# PicoHAL_-_w5500.net
KiCad netlist of a schematic drawn in Altium Designer
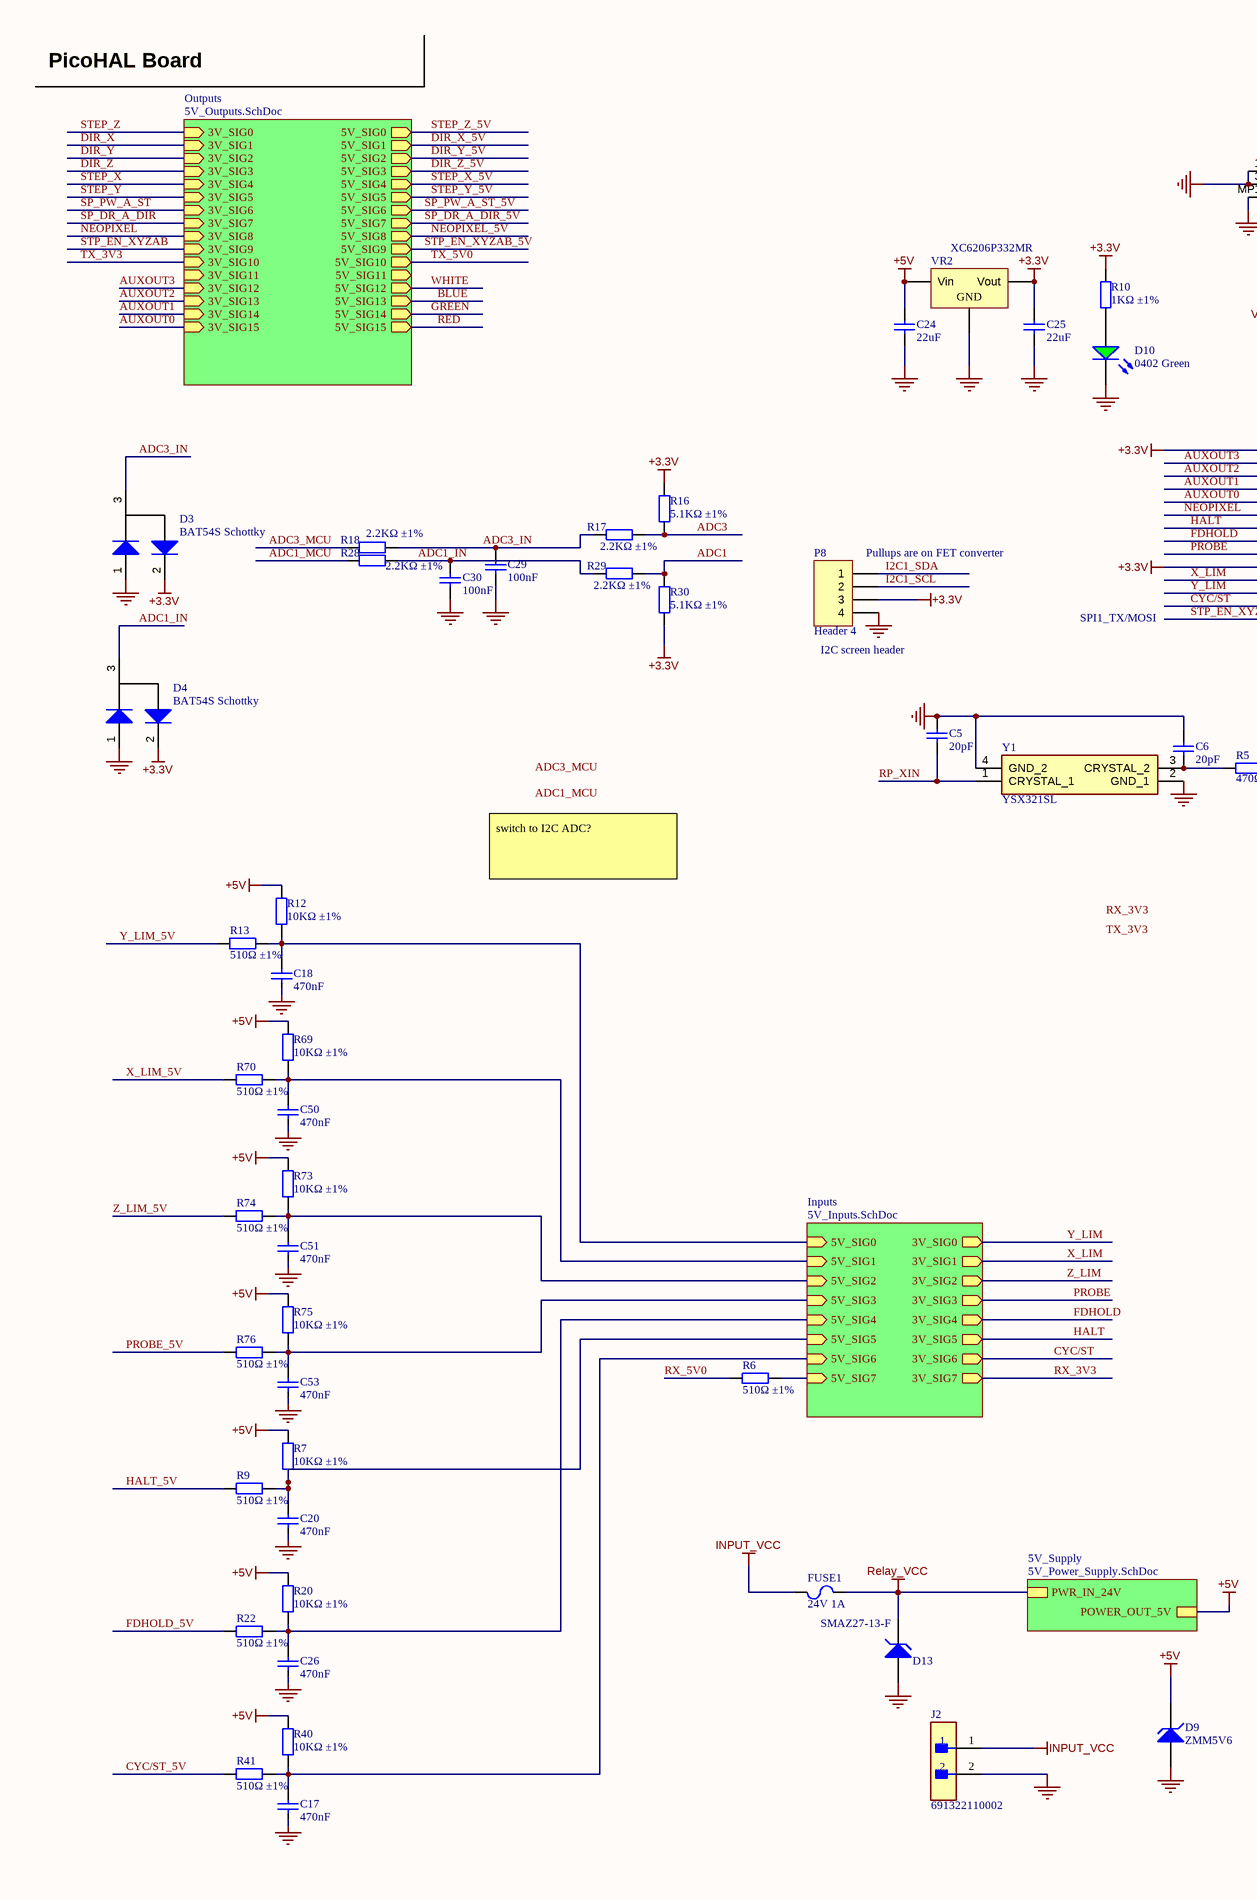
[diagram p0: PicoHAL - w5500.SchDoc, left]
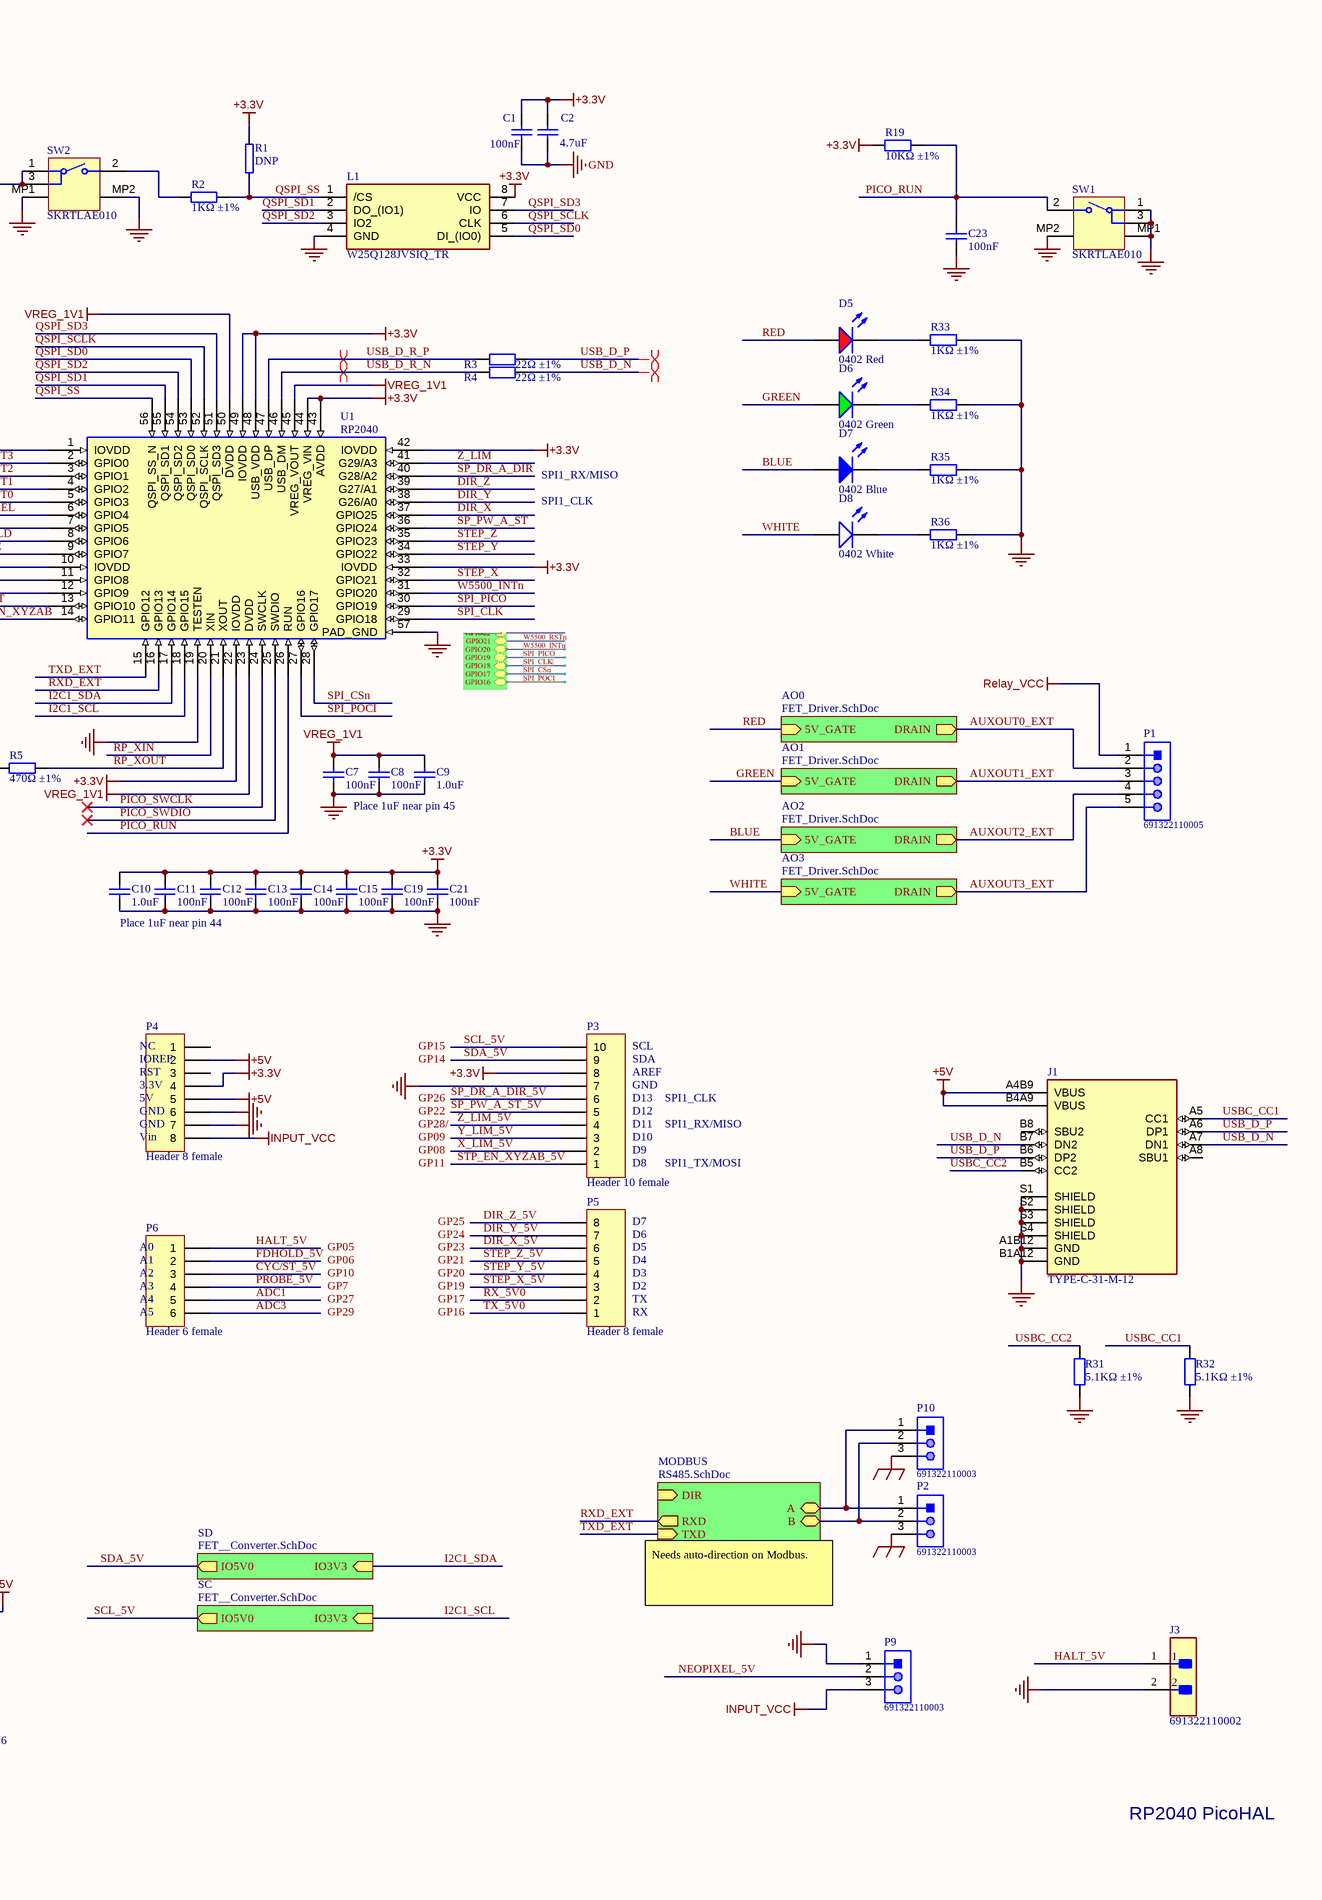
[diagram p1: PicoHAL - w5500.SchDoc, right]

(export (version "E")
  (design (tool "Eeschema 10.0.6"))
  (components
    (comp (ref "C1")
      (value "100nF")
      (footprint "0402_C")
      (description "Chip capacitors")
      (fields
        (field (name "MANUFACTURER") "Samsung Electro-Mechanics")
        (field (name "PARTNUMBER") "CL05B104KO5NNNC")
      )
      (libsource (lib "Cap") (part "0402 100nF (104) 10% 16V"))
    )
    (comp (ref "C2")
      (value "4.7uF")
      (footprint "0402_C")
      (description "Chip capacitor")
      (fields
        (field (name "MANUFACTURER") "Samsung Electro-Mechanics")
        (field (name "PARTNUMBER") "CL05A475MP5NRNC")
      )
      (libsource (lib "Cap") (part "0402 4.7uF (475) 20% 10V"))
    )
    (comp (ref "C5")
      (value "20pF")
      (footprint "0402_C")
      (description "Chip capacitors")
      (fields
        (field (name "MANUFACTURER") "Guangdong Fenghua Advanced Tech")
        (field (name "PARTNUMBER") "0402CG200J500NT")
      )
      (libsource (lib "Cap") (part "0402 20pF (200) 5% 50V"))
    )
    (comp (ref "C6")
      (value "20pF")
      (footprint "0402_C")
      (description "Chip capacitors")
      (fields
        (field (name "MANUFACTURER") "Guangdong Fenghua Advanced Tech")
        (field (name "PARTNUMBER") "0402CG200J500NT")
      )
      (libsource (lib "Cap") (part "0402 20pF (200) 5% 50V"))
    )
    (comp (ref "C7")
      (value "100nF")
      (footprint "0402_C")
      (description "Chip capacitors")
      (fields
        (field (name "MANUFACTURER") "Samsung Electro-Mechanics")
        (field (name "PARTNUMBER") "CL05B104KO5NNNC")
      )
      (libsource (lib "Cap") (part "0402 100nF (104) 10% 16V"))
    )
    (comp (ref "C8")
      (value "100nF")
      (footprint "0402_C")
      (description "Chip capacitors")
      (fields
        (field (name "MANUFACTURER") "Samsung Electro-Mechanics")
        (field (name "PARTNUMBER") "CL05B104KO5NNNC")
      )
      (libsource (lib "Cap") (part "0402 100nF (104) 10% 16V"))
    )
    (comp (ref "C9")
      (value "1.0uF")
      (footprint "0402_C")
      (description "Chip capacitor")
      (fields
        (field (name "MANUFACTURER") "Samsung Electro-Mechanics")
        (field (name "PARTNUMBER") "CL05A105KA5NQNC")
      )
      (libsource (lib "Cap") (part "0402 1.0uF (105) 10% 25V"))
    )
    (comp (ref "C10")
      (value "1.0uF")
      (footprint "0402_C")
      (description "Chip capacitor")
      (fields
        (field (name "MANUFACTURER") "Samsung Electro-Mechanics")
        (field (name "PARTNUMBER") "CL05A105KA5NQNC")
      )
      (libsource (lib "Cap") (part "0402 1.0uF (105) 10% 25V"))
    )
    (comp (ref "C11")
      (value "100nF")
      (footprint "0402_C")
      (description "Chip capacitors")
      (fields
        (field (name "MANUFACTURER") "Samsung Electro-Mechanics")
        (field (name "PARTNUMBER") "CL05B104KO5NNNC")
      )
      (libsource (lib "Cap") (part "0402 100nF (104) 10% 16V"))
    )
    (comp (ref "C12")
      (value "100nF")
      (footprint "0402_C")
      (description "Chip capacitors")
      (fields
        (field (name "MANUFACTURER") "Samsung Electro-Mechanics")
        (field (name "PARTNUMBER") "CL05B104KO5NNNC")
      )
      (libsource (lib "Cap") (part "0402 100nF (104) 10% 16V"))
    )
    (comp (ref "C13")
      (value "100nF")
      (footprint "0402_C")
      (description "Chip capacitors")
      (fields
        (field (name "MANUFACTURER") "Samsung Electro-Mechanics")
        (field (name "PARTNUMBER") "CL05B104KO5NNNC")
      )
      (libsource (lib "Cap") (part "0402 100nF (104) 10% 16V"))
    )
    (comp (ref "C14")
      (value "100nF")
      (footprint "0402_C")
      (description "Chip capacitors")
      (fields
        (field (name "MANUFACTURER") "Samsung Electro-Mechanics")
        (field (name "PARTNUMBER") "CL05B104KO5NNNC")
      )
      (libsource (lib "Cap") (part "0402 100nF (104) 10% 16V"))
    )
    (comp (ref "C15")
      (value "100nF")
      (footprint "0402_C")
      (description "Chip capacitors")
      (fields
        (field (name "MANUFACTURER") "Samsung Electro-Mechanics")
        (field (name "PARTNUMBER") "CL05B104KO5NNNC")
      )
      (libsource (lib "Cap") (part "0402 100nF (104) 10% 16V"))
    )
    (comp (ref "C17")
      (value "470nF")
      (footprint "0402_C")
      (description "Chip capacitors")
      (fields
        (field (name "MANUFACTURER") "Samsung Electro-Mechanics")
        (field (name "PARTNUMBER") "CL05A474KP5NNNC")
      )
      (libsource (lib "Cap") (part "0402 470nF (474) 10% 10V"))
    )
    (comp (ref "C18")
      (value "470nF")
      (footprint "0402_C")
      (description "Chip capacitors")
      (fields
        (field (name "MANUFACTURER") "Samsung Electro-Mechanics")
        (field (name "PARTNUMBER") "CL05A474KP5NNNC")
      )
      (libsource (lib "Cap") (part "0402 470nF (474) 10% 10V"))
    )
    (comp (ref "C19")
      (value "100nF")
      (footprint "0402_C")
      (description "Chip capacitors")
      (fields
        (field (name "MANUFACTURER") "Samsung Electro-Mechanics")
        (field (name "PARTNUMBER") "CL05B104KO5NNNC")
      )
      (libsource (lib "Cap") (part "0402 100nF (104) 10% 16V"))
    )
    (comp (ref "C20")
      (value "470nF")
      (footprint "0402_C")
      (description "Chip capacitors")
      (fields
        (field (name "MANUFACTURER") "Samsung Electro-Mechanics")
        (field (name "PARTNUMBER") "CL05A474KP5NNNC")
      )
      (libsource (lib "Cap") (part "0402 470nF (474) 10% 10V"))
    )
    (comp (ref "C21")
      (value "100nF")
      (footprint "0402_C")
      (description "Chip capacitors")
      (fields
        (field (name "MANUFACTURER") "Samsung Electro-Mechanics")
        (field (name "PARTNUMBER") "CL05B104KO5NNNC")
      )
      (libsource (lib "Cap") (part "0402 100nF (104) 10% 16V"))
    )
    (comp (ref "C23")
      (value "100nF")
      (footprint "0402_C")
      (description "Chip capacitors")
      (fields
        (field (name "MANUFACTURER") "Samsung Electro-Mechanics")
        (field (name "PARTNUMBER") "CL05B104KO5NNNC")
      )
      (libsource (lib "Cap") (part "0402 100nF (104) 10% 16V"))
    )
    (comp (ref "C24")
      (value "22uF")
      (footprint "0805_C")
      (description "Chip capacitors")
      (fields
        (field (name "MANUFACTURER") "Samsung Electro-Mechanics")
        (field (name "PARTNUMBER") "CL21A226MAQNNNE")
      )
      (libsource (lib "Cap") (part "0805 22uF (226) 20% 25V"))
    )
    (comp (ref "C25")
      (value "22uF")
      (footprint "0805_C")
      (description "Chip capacitors")
      (fields
        (field (name "MANUFACTURER") "Samsung Electro-Mechanics")
        (field (name "PARTNUMBER") "CL21A226MAQNNNE")
      )
      (libsource (lib "Cap") (part "0805 22uF (226) 20% 25V"))
    )
    (comp (ref "C26")
      (value "470nF")
      (footprint "0402_C")
      (description "Chip capacitors")
      (fields
        (field (name "MANUFACTURER") "Samsung Electro-Mechanics")
        (field (name "PARTNUMBER") "CL05A474KP5NNNC")
      )
      (libsource (lib "Cap") (part "0402 470nF (474) 10% 10V"))
    )
    (comp (ref "C29")
      (value "100nF")
      (footprint "0402_C")
      (description "Chip capacitors")
      (fields
        (field (name "MANUFACTURER") "Samsung Electro-Mechanics")
        (field (name "PARTNUMBER") "CL05B104KO5NNNC")
      )
      (libsource (lib "Cap") (part "0402 100nF (104) 10% 16V"))
    )
    (comp (ref "C30")
      (value "100nF")
      (footprint "0402_C")
      (description "Chip capacitors")
      (fields
        (field (name "MANUFACTURER") "Samsung Electro-Mechanics")
        (field (name "PARTNUMBER") "CL05B104KO5NNNC")
      )
      (libsource (lib "Cap") (part "0402 100nF (104) 10% 16V"))
    )
    (comp (ref "C50")
      (value "470nF")
      (footprint "0402_C")
      (description "Chip capacitors")
      (fields
        (field (name "MANUFACTURER") "Samsung Electro-Mechanics")
        (field (name "PARTNUMBER") "CL05A474KP5NNNC")
      )
      (libsource (lib "Cap") (part "0402 470nF (474) 10% 10V"))
    )
    (comp (ref "C51")
      (value "470nF")
      (footprint "0402_C")
      (description "Chip capacitors")
      (fields
        (field (name "MANUFACTURER") "Samsung Electro-Mechanics")
        (field (name "PARTNUMBER") "CL05A474KP5NNNC")
      )
      (libsource (lib "Cap") (part "0402 470nF (474) 10% 10V"))
    )
    (comp (ref "C53")
      (value "470nF")
      (footprint "0402_C")
      (description "Chip capacitors")
      (fields
        (field (name "MANUFACTURER") "Samsung Electro-Mechanics")
        (field (name "PARTNUMBER") "CL05A474KP5NNNC")
      )
      (libsource (lib "Cap") (part "0402 470nF (474) 10% 10V"))
    )
    (comp (ref "D3")
      (value "BAT54S Schottky")
      (footprint "SOT-23(SOT-23-3)")
      (description "30V Dual 200mA 800mV@100mA SOT-23 Schottky Barrier Diodes (SBD) ROHS")
      (libsource (lib "Diode") (part "SOT-23 BAT54S"))
    )
    (comp (ref "D4")
      (value "BAT54S Schottky")
      (footprint "SOT-23(SOT-23-3)")
      (description "30V Dual 200mA 800mV@100mA SOT-23 Schottky Barrier Diodes (SBD) ROHS")
      (libsource (lib "Diode") (part "SOT-23 BAT54S"))
    )
    (comp (ref "D5")
      (value "0402 Red")
      (footprint "LED 0402_1005 RED")
      (description "LED")
      (libsource (lib "LED") (part "0402 LED Red"))
    )
    (comp (ref "D6")
      (value "0402 Green")
      (footprint "LED 0402_1005 RED")
      (description "LED")
      (libsource (lib "LED") (part "0402 LED Green"))
    )
    (comp (ref "D7")
      (value "0402 Blue")
      (footprint "LED 0402_1005 RED")
      (description "LED")
      (libsource (lib "LED") (part "0402 LED Blue"))
    )
    (comp (ref "D8")
      (value "0402 White")
      (footprint "LED 0402_1005 RED")
      (description "LED")
      (libsource (lib "LED") (part "0402 LED White"))
    )
    (comp (ref "D9")
      (value "ZMM5V6")
      (footprint "LL-34")
      (description "500mW - 0.1uA @ 1V 5.6V LL-34 Zener Diodes ROHS")
      (libsource (lib "Zener") (part "LL-34 ZMM5V6"))
    )
    (comp (ref "D10")
      (value "0402 Green")
      (footprint "LED 0402_1005 RED")
      (description "LED")
      (libsource (lib "LED") (part "0402 LED Green"))
    )
    (comp (ref "D13")
      (value "SMAZ27-13-F")
      (footprint "DIOM5226X240N")
      (description "27V ±5% 1W 500nA @ 20.5V SMA(DO-214AC) Zener Diodes RoHS")
      (libsource (lib "PrintNC_GRBLHAL_Breakout") (part "BZT52C27"))
    )
    (comp (ref "FUSE1")
      (value "24V 1A")
      (footprint "1206_C")
      (description "24V 1A 0.1s 1206 PTC Resettable Fuses RoHS")
      (fields
        (field (name "MANUFACTURER") "Jinrui Electronic Materials Co.")
        (field (name "PARTNUMBER") "JK-nSMD050-24")
      )
      (libsource (lib "PrintNC_GRBLHAL_Breakout") (part "JK-nSMD050-24"))
    )
    (comp (ref "J1")
      (value "TYPE-C-31-M-12")
      (footprint "HRO_TYPE-C-31-M-12")
      (description "USB Connectors 24 Receptacle 1 8.94*7.3mm RoHS")
      (fields (field (name "MF") "HRO Electronics Co., Ltd."))
      (libsource (lib "Universal_CNC_Breakout") (part "TYPE-C-31-M-12"))
    )
    (comp (ref "J2")
      (value "691322110002")
      (footprint "FP-691322110002-MFG")
      (description "TERM BLOCK HDR 2POS 90DEG 3.5MM")
      (fields (field (name "VOLTAGE") "300V"))
      (libsource (lib "Altium Content Vault") (part "3bc925449376181038e59eaffc5286c"))
    )
    (comp (ref "J3")
      (value "691322110002")
      (footprint "FP-691322110002-MFG")
      (description "TERM BLOCK HDR 2POS 90DEG 3.5MM")
      (fields (field (name "VOLTAGE") "300V"))
      (libsource (lib "") (part "3bc925449376181038e59eaffc5286c_1"))
    )
    (comp (ref "L1")
      (value "W25Q128JVSIQ_TR")
      (footprint "SamacSys:SOIC127P780X195-8N")
      (description "Inductor")
      (fields
        (field (name "MANUFACTURER_PART_NUMBER") "W25Q128JVSIQ TR")
        (field (name "MOUSER PART NUMBER") "454-W25Q128JVSIQTR")
      )
      (libsource (lib "*") (part "W25Q128JVSIQ_TR"))
    )
    (comp (ref "P1")
      (value "691322110005")
      (footprint "691322110005")
      (description "Serie 3221 - 3.50mm Horizontal PCB Header WR-TBL, 5 pin")
      (fields (field (name "MANUFACTURER") "Wurth Elektronik") (field (name "PUBLISHER") "WurthElektronik"))
      (libsource (lib "Altium Content Vault") (part "WE-CN-1P-M-R5"))
    )
    (comp (ref "P2")
      (value "691322110003")
      (footprint "691322110003")
      (description "Serie 3221 - 3.50mm Horizontal PCB Header WR-TBL, 3 pin")
      (fields (field (name "MANUFACTURER") "Wurth Elektronik") (field (name "PUBLISHER") "WurthElektronik"))
      (libsource (lib "Altium Content Vault") (part "WE-CN-1P-M-R3"))
    )
    (comp (ref "P3")
      (value "Header 10 female")
      (footprint "HDR1X10")
      (description "Header, 10-Pin")
      (fields (field (name "PUBLISHER") "Altium Limited"))
      (libsource (lib "Miscellaneous Connectors") (part "Header 10"))
    )
    (comp (ref "P4")
      (value "Header 8 female")
      (footprint "HDR1X8")
      (description "Header, 8-Pin")
      (fields (field (name "PUBLISHER") "Altium Limited"))
      (libsource (lib "") (part "Header 8_1"))
    )
    (comp (ref "P5")
      (value "Header 8 female")
      (footprint "HDR1X8")
      (description "Header, 8-Pin")
      (fields (field (name "PUBLISHER") "Altium Limited"))
      (libsource (lib "Miscellaneous Connectors") (part "Header 8"))
    )
    (comp (ref "P6")
      (value "Header 6 female")
      (footprint "HDR1X6")
      (description "Header, 6-Pin")
      (fields (field (name "PUBLISHER") "Altium Limited"))
      (libsource (lib "Miscellaneous Connectors") (part "Header 6"))
    )
    (comp (ref "P8")
      (value "Header 4")
      (footprint "HDR1X4")
      (description "Header, 4-Pin F")
      (fields (field (name "PUBLISHER") "Altium Limited"))
      (libsource (lib "PrintNC_GRBLHAL_Breakout") (part "Header 4"))
    )
    (comp (ref "P9")
      (value "691322110003")
      (footprint "691322110003")
      (description "Serie 3221 - 3.50mm Horizontal PCB Header WR-TBL, 3 pin")
      (fields (field (name "MANUFACTURER") "Wurth Elektronik") (field (name "PUBLISHER") "WurthElektronik"))
      (libsource (lib "Altium Content Vault") (part "WE-CN-1P-M-R3"))
    )
    (comp (ref "P10")
      (value "691322110003")
      (footprint "691322110003")
      (description "Serie 3221 - 3.50mm Horizontal PCB Header WR-TBL, 3 pin")
      (fields (field (name "MANUFACTURER") "Wurth Elektronik") (field (name "PUBLISHER") "WurthElektronik"))
      (libsource (lib "Altium Content Vault") (part "WE-CN-1P-M-R3"))
    )
    (comp (ref "R1")
      (value "DNP")
      (footprint "0402")
      (description "Resistor, ±5%, 0.05W")
      (fields (field (name "PART NUMBER") "R0201-0R") (field (name "PUBLISHER") "Nordic Semiconductor"))
      (libsource (lib "Passives") (part "RES"))
    )
    (comp (ref "R2")
      (value "1KΩ ±1%")
      (footprint "0402_R")
      (description "Chip resistor")
      (fields (field (name "MANUFACTURER") "Uniroyal Elec") (field (name "PARTNUMBER") "0402WGF1001TCE"))
      (libsource (lib "RES") (part "0402 1K (1001) 1%"))
    )
    (comp (ref "R3")
      (value "22Ω ±1%")
      (footprint "0402_R")
      (description "Chip resistor")
      (fields (field (name "MANUFACTURER") "Uniroyal Elec") (field (name "PARTNUMBER") "0402WGF220JTCE"))
      (libsource (lib "RES") (part "0402 22R (22R0) 1%"))
    )
    (comp (ref "R4")
      (value "22Ω ±1%")
      (footprint "0402_R")
      (description "Chip resistor")
      (fields (field (name "MANUFACTURER") "Uniroyal Elec") (field (name "PARTNUMBER") "0402WGF220JTCE"))
      (libsource (lib "RES") (part "0402 22R (22R0) 1%"))
    )
    (comp (ref "R5")
      (value "470Ω ±1%")
      (footprint "0402_R")
      (description "Chip resistor")
      (fields (field (name "MANUFACTURER") "Uniroyal Elec") (field (name "PARTNUMBER") "0402WGF4700TCE"))
      (libsource (lib "RES") (part "0402 470R (4700) 1%"))
    )
    (comp (ref "R6")
      (value "510Ω ±1%")
      (footprint "0402_R")
      (description "Chip resistor")
      (fields (field (name "MANUFACTURER") "Uniroyal Elec") (field (name "PARTNUMBER") "0402WGF5100TCE"))
      (libsource (lib "RES") (part "0402 510R (5100) 1%"))
    )
    (comp (ref "R7")
      (value "10KΩ ±1%")
      (footprint "0402_R")
      (description "Chip resistor")
      (fields (field (name "MANUFACTURER") "Uniroyal Elec") (field (name "PARTNUMBER") "0402WGF1002TCE"))
      (libsource (lib "RES") (part "0402 10K (1002) 1%"))
    )
    (comp (ref "R9")
      (value "510Ω ±1%")
      (footprint "0402_R")
      (description "Chip resistor")
      (fields (field (name "MANUFACTURER") "Uniroyal Elec") (field (name "PARTNUMBER") "0402WGF5100TCE"))
      (libsource (lib "RES") (part "0402 510R (5100) 1%"))
    )
    (comp (ref "R10")
      (value "1KΩ ±1%")
      (footprint "0402_R")
      (description "Chip resistor")
      (fields (field (name "MANUFACTURER") "Uniroyal Elec") (field (name "PARTNUMBER") "0402WGF1001TCE"))
      (libsource (lib "") (part "0402 1K (1001) 1%_1"))
    )
    (comp (ref "R12")
      (value "10KΩ ±1%")
      (footprint "0402_R")
      (description "Chip resistor")
      (fields (field (name "MANUFACTURER") "Uniroyal Elec") (field (name "PARTNUMBER") "0402WGF1002TCE"))
      (libsource (lib "RES") (part "0402 10K (1002) 1%"))
    )
    (comp (ref "R13")
      (value "510Ω ±1%")
      (footprint "0402_R")
      (description "Chip resistor")
      (fields (field (name "MANUFACTURER") "Uniroyal Elec") (field (name "PARTNUMBER") "0402WGF5100TCE"))
      (libsource (lib "RES") (part "0402 510R (5100) 1%"))
    )
    (comp (ref "R16")
      (value "5.1KΩ ±1%")
      (footprint "0402_R")
      (description "Chip resistor")
      (fields (field (name "MANUFACTURER") "Uniroyal Elec") (field (name "PARTNUMBER") "0402WGF5101TCE"))
      (libsource (lib "RES") (part "0402 5.1K (5101) 1%"))
    )
    (comp (ref "R17")
      (value "2.2KΩ ±1%")
      (footprint "0402_R")
      (description "Chip resistor")
      (fields (field (name "MANUFACTURER") "Uniroyal Elec") (field (name "PARTNUMBER") "0402WGF2201TCE"))
      (libsource (lib "RES") (part "0402 2.2K (2201) 1%"))
    )
    (comp (ref "R18")
      (value "2.2KΩ ±1%")
      (footprint "0402_R")
      (description "Chip resistor")
      (fields (field (name "MANUFACTURER") "Uniroyal Elec") (field (name "PARTNUMBER") "0402WGF2201TCE"))
      (libsource (lib "RES") (part "0402 2.2K (2201) 1%"))
    )
    (comp (ref "R19")
      (value "10KΩ ±1%")
      (footprint "0402_R")
      (description "Chip resistor")
      (fields (field (name "MANUFACTURER") "Uniroyal Elec") (field (name "PARTNUMBER") "0402WGF1002TCE"))
      (libsource (lib "") (part "0402 10K (1002) 1%_1"))
    )
    (comp (ref "R20")
      (value "10KΩ ±1%")
      (footprint "0402_R")
      (description "Chip resistor")
      (fields (field (name "MANUFACTURER") "Uniroyal Elec") (field (name "PARTNUMBER") "0402WGF1002TCE"))
      (libsource (lib "RES") (part "0402 10K (1002) 1%"))
    )
    (comp (ref "R22")
      (value "510Ω ±1%")
      (footprint "0402_R")
      (description "Chip resistor")
      (fields (field (name "MANUFACTURER") "Uniroyal Elec") (field (name "PARTNUMBER") "0402WGF5100TCE"))
      (libsource (lib "RES") (part "0402 510R (5100) 1%"))
    )
    (comp (ref "R28")
      (value "2.2KΩ ±1%")
      (footprint "0402_R")
      (description "Chip resistor")
      (fields (field (name "MANUFACTURER") "Uniroyal Elec") (field (name "PARTNUMBER") "0402WGF2201TCE"))
      (libsource (lib "RES") (part "0402 2.2K (2201) 1%"))
    )
    (comp (ref "R29")
      (value "2.2KΩ ±1%")
      (footprint "0402_R")
      (description "Chip resistor")
      (fields (field (name "MANUFACTURER") "Uniroyal Elec") (field (name "PARTNUMBER") "0402WGF2201TCE"))
      (libsource (lib "RES") (part "0402 2.2K (2201) 1%"))
    )
    (comp (ref "R30")
      (value "5.1KΩ ±1%")
      (footprint "0402_R")
      (description "Chip resistor")
      (fields (field (name "MANUFACTURER") "Uniroyal Elec") (field (name "PARTNUMBER") "0402WGF5101TCE"))
      (libsource (lib "RES") (part "0402 5.1K (5101) 1%"))
    )
    (comp (ref "R31")
      (value "5.1KΩ ±1%")
      (footprint "0402_R")
      (description "Chip resistor")
      (fields (field (name "MANUFACTURER") "Uniroyal Elec") (field (name "PARTNUMBER") "0402WGF5101TCE"))
      (libsource (lib "RES") (part "0402 5.1K (5101) 1%"))
    )
    (comp (ref "R32")
      (value "5.1KΩ ±1%")
      (footprint "0402_R")
      (description "Chip resistor")
      (fields (field (name "MANUFACTURER") "Uniroyal Elec") (field (name "PARTNUMBER") "0402WGF5101TCE"))
      (libsource (lib "RES") (part "0402 5.1K (5101) 1%"))
    )
    (comp (ref "R33")
      (value "1KΩ ±1%")
      (footprint "0402_R")
      (description "Chip resistor")
      (fields (field (name "MANUFACTURER") "Uniroyal Elec") (field (name "PARTNUMBER") "0402WGF1001TCE"))
      (libsource (lib "RES") (part "0402 1K (1001) 1%"))
    )
    (comp (ref "R34")
      (value "1KΩ ±1%")
      (footprint "0402_R")
      (description "Chip resistor")
      (fields (field (name "MANUFACTURER") "Uniroyal Elec") (field (name "PARTNUMBER") "0402WGF1001TCE"))
      (libsource (lib "RES") (part "0402 1K (1001) 1%"))
    )
    (comp (ref "R35")
      (value "1KΩ ±1%")
      (footprint "0402_R")
      (description "Chip resistor")
      (fields (field (name "MANUFACTURER") "Uniroyal Elec") (field (name "PARTNUMBER") "0402WGF1001TCE"))
      (libsource (lib "RES") (part "0402 1K (1001) 1%"))
    )
    (comp (ref "R36")
      (value "1KΩ ±1%")
      (footprint "0402_R")
      (description "Chip resistor")
      (fields (field (name "MANUFACTURER") "Uniroyal Elec") (field (name "PARTNUMBER") "0402WGF1001TCE"))
      (libsource (lib "RES") (part "0402 1K (1001) 1%"))
    )
    (comp (ref "R40")
      (value "10KΩ ±1%")
      (footprint "0402_R")
      (description "Chip resistor")
      (fields (field (name "MANUFACTURER") "Uniroyal Elec") (field (name "PARTNUMBER") "0402WGF1002TCE"))
      (libsource (lib "RES") (part "0402 10K (1002) 1%"))
    )
    (comp (ref "R41")
      (value "510Ω ±1%")
      (footprint "0402_R")
      (description "Chip resistor")
      (fields (field (name "MANUFACTURER") "Uniroyal Elec") (field (name "PARTNUMBER") "0402WGF5100TCE"))
      (libsource (lib "RES") (part "0402 510R (5100) 1%"))
    )
    (comp (ref "R69")
      (value "10KΩ ±1%")
      (footprint "0402_R")
      (description "Chip resistor")
      (fields (field (name "MANUFACTURER") "Uniroyal Elec") (field (name "PARTNUMBER") "0402WGF1002TCE"))
      (libsource (lib "RES") (part "0402 10K (1002) 1%"))
    )
    (comp (ref "R70")
      (value "510Ω ±1%")
      (footprint "0402_R")
      (description "Chip resistor")
      (fields (field (name "MANUFACTURER") "Uniroyal Elec") (field (name "PARTNUMBER") "0402WGF5100TCE"))
      (libsource (lib "RES") (part "0402 510R (5100) 1%"))
    )
    (comp (ref "R73")
      (value "10KΩ ±1%")
      (footprint "0402_R")
      (description "Chip resistor")
      (fields (field (name "MANUFACTURER") "Uniroyal Elec") (field (name "PARTNUMBER") "0402WGF1002TCE"))
      (libsource (lib "RES") (part "0402 10K (1002) 1%"))
    )
    (comp (ref "R74")
      (value "510Ω ±1%")
      (footprint "0402_R")
      (description "Chip resistor")
      (fields (field (name "MANUFACTURER") "Uniroyal Elec") (field (name "PARTNUMBER") "0402WGF5100TCE"))
      (libsource (lib "RES") (part "0402 510R (5100) 1%"))
    )
    (comp (ref "R75")
      (value "10KΩ ±1%")
      (footprint "0402_R")
      (description "Chip resistor")
      (fields (field (name "MANUFACTURER") "Uniroyal Elec") (field (name "PARTNUMBER") "0402WGF1002TCE"))
      (libsource (lib "RES") (part "0402 10K (1002) 1%"))
    )
    (comp (ref "R76")
      (value "510Ω ±1%")
      (footprint "0402_R")
      (description "Chip resistor")
      (fields (field (name "MANUFACTURER") "Uniroyal Elec") (field (name "PARTNUMBER") "0402WGF5100TCE"))
      (libsource (lib "RES") (part "0402 510R (5100) 1%"))
    )
    (comp (ref "SW1")
      (value "SKRTLAE010")
      (footprint "ALPS-SKRTLAE010_V")
      (description "Side Push Type, 250 V, -40 to 90 degC, 3-Pin SMD, RoHS, Tape and Reel")
      (fields (field (name "MANUFACTURER") "ALPS"))
      (libsource (lib "Altium Content Vault") (part "SW_SPST-3_A"))
    )
    (comp (ref "SW2")
      (value "SKRTLAE010")
      (footprint "ALPS-SKRTLAE010_V")
      (description "Side Push Type, 250 V, -40 to 90 degC, 3-Pin SMD, RoHS, Tape and Reel")
      (fields (field (name "MANUFACTURER") "ALPS"))
      (libsource (lib "") (part "SW_SPST-3_A_1"))
    )
    (comp (ref "U1")
      (value "RP2040")
      (footprint "RP2040")
      (description "RP2040 First MCU from RPI")
      (libsource (lib "Universal_CNC_Breakout") (part "RP2040"))
    )
    (comp (ref "VR2")
      (value "XC6206P332MR")
      (footprint "SOT-23-3L")
      (description "200mA 680mV@(100mA) Fixed 3.3V~3.3V Positive 1 6V SOT-23-3L Linear Voltage Regulators (LDO) ROHS")
      (libsource (lib "LDO") (part "SOT-23 XC6206P332MR"))
    )
    (comp (ref "Y1")
      (value "YSX321SL")
      (footprint "SamacSys:YSX321SL")
      (description "Crystal or Oscillator")
      (libsource (lib "*") (part "YSX321SL"))
    )
  )
  (nets
    (net (code "1") (name "+3.3V") (class "Default")
      (node (ref "C1") (pin "2") (pinfunction "2_2") (pintype "passive"))
      (node (ref "C10") (pin "2") (pinfunction "2_2") (pintype "passive"))
      (node (ref "C11") (pin "2") (pinfunction "2_2") (pintype "passive"))
      (node (ref "C12") (pin "2") (pinfunction "2_2") (pintype "passive"))
      (node (ref "C13") (pin "2") (pinfunction "2_2") (pintype "passive"))
      (node (ref "C14") (pin "2") (pinfunction "2_2") (pintype "passive"))
      (node (ref "C15") (pin "2") (pinfunction "2_2") (pintype "passive"))
      (node (ref "C19") (pin "2") (pinfunction "2_2") (pintype "passive"))
      (node (ref "C2") (pin "2") (pinfunction "2_2") (pintype "passive"))
      (node (ref "C21") (pin "2") (pinfunction "2_2") (pintype "passive"))
      (node (ref "C25") (pin "2") (pinfunction "2_2") (pintype "passive"))
      (node (ref "D3") (pin "2") (pinfunction "A_2") (pintype "passive"))
      (node (ref "D4") (pin "2") (pinfunction "A_2") (pintype "passive"))
      (node (ref "L1") (pin "8") (pinfunction "VCC_8") (pintype "passive"))
      (node (ref "P3") (pin "8") (pinfunction "8_8") (pintype "passive"))
      (node (ref "P4") (pin "4") (pinfunction "4_4") (pintype "passive"))
      (node (ref "P8") (pin "3") (pinfunction "3_3") (pintype "passive"))
      (node (ref "R1") (pin "2") (pinfunction "2_2") (pintype "passive"))
      (node (ref "R10") (pin "2") (pinfunction "2_2") (pintype "passive"))
      (node (ref "R16") (pin "1") (pinfunction "1_1") (pintype "passive"))
      (node (ref "R19") (pin "2") (pinfunction "2_2") (pintype "passive"))
      (node (ref "R30") (pin "2") (pinfunction "2_2") (pintype "passive"))
      (node (ref "U1") (pin "1") (pinfunction "IOVDD_1") (pintype "input"))
      (node (ref "U1") (pin "10") (pinfunction "IOVDD_10") (pintype "input"))
      (node (ref "U1") (pin "22") (pinfunction "IOVDD_22") (pintype "input"))
      (node (ref "U1") (pin "33") (pinfunction "IOVDD_33") (pintype "input"))
      (node (ref "U1") (pin "42") (pinfunction "IOVDD_42") (pintype "input"))
      (node (ref "U1") (pin "43") (pinfunction "AVDD_43") (pintype "input"))
      (node (ref "U1") (pin "44") (pinfunction "VREG_VIN_44") (pintype "input"))
      (node (ref "U1") (pin "48") (pinfunction "USB_VDD_48") (pintype "input"))
      (node (ref "U1") (pin "49") (pinfunction "IOVDD_49") (pintype "input"))
      (node (ref "VR2") (pin "2") (pinfunction "Vout_2") (pintype "passive"))
    )
    (net (code "2") (name "+5V") (class "Default")
      (node (ref "C24") (pin "2") (pinfunction "2_2") (pintype "passive"))
      (node (ref "D9") (pin "2") (pinfunction "K_2") (pintype "passive"))
      (node (ref "J1") (pin "A4B9") (pinfunction "VBUS_A4B9") (pintype "power_in"))
      (node (ref "J1") (pin "B4A9") (pinfunction "VBUS_B4A9") (pintype "power_in"))
      (node (ref "P4") (pin "2") (pinfunction "2_2") (pintype "passive"))
      (node (ref "P4") (pin "5") (pinfunction "5_5") (pintype "passive"))
      (node (ref "R12") (pin "2") (pinfunction "2_2") (pintype "passive"))
      (node (ref "R20") (pin "2") (pinfunction "2_2") (pintype "passive"))
      (node (ref "R40") (pin "2") (pinfunction "2_2") (pintype "passive"))
      (node (ref "R69") (pin "2") (pinfunction "2_2") (pintype "passive"))
      (node (ref "R7") (pin "2") (pinfunction "2_2") (pintype "passive"))
      (node (ref "R73") (pin "2") (pinfunction "2_2") (pintype "passive"))
      (node (ref "R75") (pin "2") (pinfunction "2_2") (pintype "passive"))
      (node (ref "VR2") (pin "3") (pinfunction "Vin_3") (pintype "passive"))
    )
    (net (code "4") (name "/5V_SIG0") (class "Default")
      (node (ref "C18") (pin "2") (pinfunction "2_2") (pintype "passive"))
      (node (ref "R12") (pin "1") (pinfunction "1_1") (pintype "passive"))
      (node (ref "R13") (pin "2") (pinfunction "2_2") (pintype "passive"))
    )
    (net (code "5") (name "/5V_SIG1") (class "Default")
      (node (ref "C50") (pin "2") (pinfunction "2_2") (pintype "passive"))
      (node (ref "R69") (pin "1") (pinfunction "1_1") (pintype "passive"))
      (node (ref "R70") (pin "2") (pinfunction "2_2") (pintype "passive"))
    )
    (net (code "6") (name "/5V_SIG2") (class "Default")
      (node (ref "C51") (pin "2") (pinfunction "2_2") (pintype "passive"))
      (node (ref "R73") (pin "1") (pinfunction "1_1") (pintype "passive"))
      (node (ref "R74") (pin "2") (pinfunction "2_2") (pintype "passive"))
    )
    (net (code "7") (name "/5V_SIG3") (class "Default")
      (node (ref "C53") (pin "2") (pinfunction "2_2") (pintype "passive"))
      (node (ref "R75") (pin "1") (pinfunction "1_1") (pintype "passive"))
      (node (ref "R76") (pin "2") (pinfunction "2_2") (pintype "passive"))
    )
    (net (code "8") (name "/5V_SIG4") (class "Default")
      (node (ref "C26") (pin "2") (pinfunction "2_2") (pintype "passive"))
      (node (ref "R20") (pin "1") (pinfunction "1_1") (pintype "passive"))
      (node (ref "R22") (pin "2") (pinfunction "2_2") (pintype "passive"))
    )
    (net (code "9") (name "/5V_SIG5") (class "Default")
      (node (ref "C20") (pin "2") (pinfunction "2_2") (pintype "passive"))
      (node (ref "R7") (pin "1") (pinfunction "1_1") (pintype "passive"))
      (node (ref "R9") (pin "2") (pinfunction "2_2") (pintype "passive"))
    )
    (net (code "10") (name "/5V_SIG6") (class "Default")
      (node (ref "C17") (pin "2") (pinfunction "2_2") (pintype "passive"))
      (node (ref "R40") (pin "1") (pinfunction "1_1") (pintype "passive"))
      (node (ref "R41") (pin "2") (pinfunction "2_2") (pintype "passive"))
    )
    (net (code "11") (name "/5V_SIG7") (class "Default")
      (node (ref "R6") (pin "2") (pinfunction "2_2") (pintype "passive"))
    )
    (net (code "13") (name "/A") (class "Default")
      (node (ref "P10") (pin "1") (pinfunction "1_1") (pintype "passive"))
      (node (ref "P2") (pin "1") (pinfunction "1_1") (pintype "passive"))
    )
    (net (code "14") (name "/ADC1") (class "Default")
      (node (ref "P6") (pin "5") (pinfunction "5_5") (pintype "passive"))
      (node (ref "R29") (pin "2") (pinfunction "2_2") (pintype "passive"))
      (node (ref "R30") (pin "1") (pinfunction "1_1") (pintype "passive"))
    )
    (net (code "15") (name "/ADC1_IN") (class "Default")
      (node (ref "C30") (pin "2") (pinfunction "2_2") (pintype "passive"))
      (node (ref "D4") (pin "3") (pinfunction "K_3") (pintype "passive"))
      (node (ref "R28") (pin "2") (pinfunction "2_2") (pintype "passive"))
      (node (ref "R29") (pin "1") (pinfunction "1_1") (pintype "passive"))
    )
    (net (code "16") (name "/ADC1_MCU") (class "Default")
      (node (ref "R28") (pin "1") (pinfunction "1_1") (pintype "passive"))
    )
    (net (code "17") (name "/ADC3") (class "Default")
      (node (ref "P6") (pin "6") (pinfunction "6_6") (pintype "passive"))
      (node (ref "R16") (pin "2") (pinfunction "2_2") (pintype "passive"))
      (node (ref "R17") (pin "2") (pinfunction "2_2") (pintype "passive"))
    )
    (net (code "18") (name "/ADC3_IN") (class "Default")
      (node (ref "C29") (pin "2") (pinfunction "2_2") (pintype "passive"))
      (node (ref "D3") (pin "3") (pinfunction "K_3") (pintype "passive"))
      (node (ref "R17") (pin "1") (pinfunction "1_1") (pintype "passive"))
      (node (ref "R18") (pin "2") (pinfunction "2_2") (pintype "passive"))
    )
    (net (code "19") (name "/ADC3_MCU") (class "Default")
      (node (ref "R18") (pin "1") (pinfunction "1_1") (pintype "passive"))
    )
    (net (code "20") (name "/AUXOUT0") (class "Default")
      (node (ref "U1") (pin "5") (pinfunction "GPIO3_5") (pintype "bidirectional"))
    )
    (net (code "21") (name "/AUXOUT0_EXT") (class "Default")
      (node (ref "P1") (pin "2") (pinfunction "2_2") (pintype "passive"))
    )
    (net (code "22") (name "/AUXOUT1") (class "Default")
      (node (ref "U1") (pin "4") (pinfunction "GPIO2_4") (pintype "bidirectional"))
    )
    (net (code "23") (name "/AUXOUT1_EXT") (class "Default")
      (node (ref "P1") (pin "3") (pinfunction "3_3") (pintype "passive"))
    )
    (net (code "24") (name "/AUXOUT2") (class "Default")
      (node (ref "U1") (pin "3") (pinfunction "GPIO1_3") (pintype "bidirectional"))
    )
    (net (code "25") (name "/AUXOUT2_EXT") (class "Default")
      (node (ref "P1") (pin "4") (pinfunction "4_4") (pintype "passive"))
    )
    (net (code "26") (name "/AUXOUT3") (class "Default")
      (node (ref "U1") (pin "2") (pinfunction "GPIO0_2") (pintype "bidirectional"))
    )
    (net (code "27") (name "/AUXOUT3_EXT") (class "Default")
      (node (ref "P1") (pin "5") (pinfunction "5_5") (pintype "passive"))
    )
    (net (code "28") (name "/B") (class "Default")
      (node (ref "P10") (pin "2") (pinfunction "2_2") (pintype "passive"))
      (node (ref "P2") (pin "2") (pinfunction "2_2") (pintype "passive"))
    )
    (net (code "29") (name "/BLUE") (class "Default")
      (node (ref "D7") (pin "A") (pinfunction "A_A") (pintype "passive"))
    )
    (net (code "30") (name "/CYC{slash}ST") (class "Default")
      (node (ref "U1") (pin "13") (pinfunction "GPIO10_13") (pintype "bidirectional"))
    )
    (net (code "31") (name "/CYC{slash}ST_5V") (class "Default")
      (node (ref "P6") (pin "3") (pinfunction "3_3") (pintype "passive"))
      (node (ref "R41") (pin "1") (pinfunction "1_1") (pintype "passive"))
    )
    (net (code "33") (name "/DIR_X") (class "Default")
      (node (ref "U1") (pin "37") (pinfunction "GPIO25_37") (pintype "bidirectional"))
    )
    (net (code "34") (name "/DIR_X_5V") (class "Default")
      (node (ref "P5") (pin "6") (pinfunction "6_6") (pintype "passive"))
    )
    (net (code "35") (name "/DIR_Y") (class "Default")
      (node (ref "U1") (pin "38") (pinfunction "G26/A0_38") (pintype "bidirectional"))
    )
    (net (code "36") (name "/DIR_Y_5V") (class "Default")
      (node (ref "P5") (pin "7") (pinfunction "7_7") (pintype "passive"))
    )
    (net (code "37") (name "/DIR_Z") (class "Default")
      (node (ref "U1") (pin "39") (pinfunction "G27/A1_39") (pintype "bidirectional"))
    )
    (net (code "38") (name "/DIR_Z_5V") (class "Default")
      (node (ref "P5") (pin "8") (pinfunction "8_8") (pintype "passive"))
    )
    (net (code "39") (name "/FDHOLD") (class "Default")
      (node (ref "U1") (pin "8") (pinfunction "GPIO6_8") (pintype "bidirectional"))
    )
    (net (code "40") (name "/FDHOLD_5V") (class "Default")
      (node (ref "P6") (pin "2") (pinfunction "2_2") (pintype "passive"))
      (node (ref "R22") (pin "1") (pinfunction "1_1") (pintype "passive"))
    )
    (net (code "41") (name "/GREEN") (class "Default")
      (node (ref "D6") (pin "A") (pinfunction "A_A") (pintype "passive"))
    )
    (net (code "42") (name "/HALT") (class "Default")
      (node (ref "U1") (pin "7") (pinfunction "GPIO5_7") (pintype "bidirectional"))
    )
    (net (code "43") (name "/HALT_5V") (class "Default")
      (node (ref "J3") (pin "1") (pinfunction "1_1") (pintype "passive"))
      (node (ref "P6") (pin "1") (pinfunction "1_1") (pintype "passive"))
      (node (ref "R9") (pin "1") (pinfunction "1_1") (pintype "passive"))
    )
    (net (code "44") (name "/I2C1_SCL") (class "Default")
      (node (ref "P8") (pin "2") (pinfunction "2_2") (pintype "passive"))
      (node (ref "U1") (pin "18") (pinfunction "GPIO15_18") (pintype "input"))
    )
    (net (code "45") (name "/I2C1_SDA") (class "Default")
      (node (ref "P8") (pin "1") (pinfunction "1_1") (pintype "passive"))
      (node (ref "U1") (pin "17") (pinfunction "GPIO14_17") (pintype "input"))
    )
    (net (code "46") (name "/NEOPIXEL") (class "Default")
      (node (ref "U1") (pin "6") (pinfunction "GPIO4_6") (pintype "bidirectional"))
    )
    (net (code "47") (name "/NEOPIXEL_5V") (class "Default")
      (node (ref "P9") (pin "2") (pinfunction "2_2") (pintype "passive"))
    )
    (net (code "48") (name "/PICO_RUN") (class "Default")
      (node (ref "C23") (pin "2") (pinfunction "2_2") (pintype "passive"))
      (node (ref "R19") (pin "1") (pinfunction "1_1") (pintype "passive"))
      (node (ref "SW1") (pin "2") (pinfunction "2_2") (pintype "passive"))
      (node (ref "U1") (pin "26") (pinfunction "RUN_26") (pintype "input"))
    )
    (net (code "49") (name "/PICO_SWCLK") (class "Default")
      (node (ref "U1") (pin "24") (pinfunction "SWCLK_24") (pintype "input+no_connect"))
    )
    (net (code "50") (name "/PICO_SWDIO") (class "Default")
      (node (ref "U1") (pin "25") (pinfunction "SWDIO_25") (pintype "input+no_connect"))
    )
    (net (code "51") (name "/PROBE") (class "Default")
      (node (ref "U1") (pin "9") (pinfunction "GPIO7_9") (pintype "bidirectional"))
    )
    (net (code "52") (name "/PROBE_5V") (class "Default")
      (node (ref "P6") (pin "4") (pinfunction "4_4") (pintype "passive"))
      (node (ref "R76") (pin "1") (pinfunction "1_1") (pintype "passive"))
    )
    (net (code "53") (name "/QSPI_SCLK") (class "Default")
      (node (ref "L1") (pin "6") (pinfunction "CLK_6") (pintype "passive"))
      (node (ref "U1") (pin "52") (pinfunction "QSPI_SCLK_52") (pintype "input"))
    )
    (net (code "54") (name "/QSPI_SD0") (class "Default")
      (node (ref "L1") (pin "5") (pinfunction "DI_(IO0)_5") (pintype "passive"))
      (node (ref "U1") (pin "53") (pinfunction "QSPI_SD0_53") (pintype "input"))
    )
    (net (code "55") (name "/QSPI_SD1") (class "Default")
      (node (ref "L1") (pin "2") (pinfunction "DO_(IO1)_2") (pintype "passive"))
      (node (ref "U1") (pin "55") (pinfunction "QSPI_SD1_55") (pintype "input"))
    )
    (net (code "56") (name "/QSPI_SD2") (class "Default")
      (node (ref "L1") (pin "3") (pinfunction "IO2_3") (pintype "passive"))
      (node (ref "U1") (pin "54") (pinfunction "QSPI_SD2_54") (pintype "input"))
    )
    (net (code "57") (name "/QSPI_SD3") (class "Default")
      (node (ref "L1") (pin "7") (pinfunction "IO_7") (pintype "passive"))
      (node (ref "U1") (pin "51") (pinfunction "QSPI_SD3_51") (pintype "input"))
    )
    (net (code "58") (name "/QSPI_SS") (class "Default")
      (node (ref "L1") (pin "1") (pinfunction "/CS_1") (pintype "passive"))
      (node (ref "R1") (pin "1") (pinfunction "1_1") (pintype "passive"))
      (node (ref "R2") (pin "2") (pinfunction "2_2") (pintype "passive"))
      (node (ref "U1") (pin "56") (pinfunction "QSPI_SS_N_56") (pintype "input"))
    )
    (net (code "59") (name "/RED") (class "Default")
      (node (ref "D5") (pin "A") (pinfunction "A_A") (pintype "passive"))
    )
    (net (code "60") (name "/RP_XIN") (class "Default")
      (node (ref "C5") (pin "1") (pinfunction "1_1") (pintype "passive"))
      (node (ref "U1") (pin "20") (pinfunction "XIN_20") (pintype "input"))
      (node (ref "Y1") (pin "1") (pinfunction "CRYSTAL_1_1") (pintype "passive"))
    )
    (net (code "61") (name "/RP_XOUT") (class "Default")
      (node (ref "R5") (pin "2") (pinfunction "2_2") (pintype "passive"))
      (node (ref "U1") (pin "21") (pinfunction "XOUT_21") (pintype "input"))
    )
    (net (code "62") (name "/RXD_EXT") (class "Default")
      (node (ref "U1") (pin "16") (pinfunction "GPIO13_16") (pintype "input"))
    )
    (net (code "64") (name "/RX_5V0") (class "Default")
      (node (ref "P5") (pin "2") (pinfunction "2_2") (pintype "passive"))
      (node (ref "R6") (pin "1") (pinfunction "1_1") (pintype "passive"))
    )
    (net (code "65") (name "/SCL_5V") (class "Default")
      (node (ref "P3") (pin "10") (pinfunction "10_10") (pintype "passive"))
    )
    (net (code "66") (name "/SDA_5V") (class "Default")
      (node (ref "P3") (pin "9") (pinfunction "9_9") (pintype "passive"))
    )
    (net (code "67") (name "/SPI_CLK") (class "Default")
      (node (ref "U1") (pin "29") (pinfunction "GPIO18_29") (pintype "bidirectional"))
    )
    (net (code "68") (name "/SPI_CSn") (class "Default")
      (node (ref "U1") (pin "28") (pinfunction "GPIO17_28") (pintype "bidirectional"))
    )
    (net (code "69") (name "/SPI_PICO") (class "Default")
      (node (ref "U1") (pin "30") (pinfunction "GPIO19_30") (pintype "bidirectional"))
    )
    (net (code "70") (name "/SPI_POCI") (class "Default")
      (node (ref "U1") (pin "27") (pinfunction "GPIO16_27") (pintype "bidirectional"))
    )
    (net (code "71") (name "/SP_DR_A_DIR") (class "Default")
      (node (ref "U1") (pin "40") (pinfunction "G28/A2_40") (pintype "bidirectional"))
    )
    (net (code "72") (name "/SP_DR_A_DIR_5V") (class "Default")
      (node (ref "P3") (pin "6") (pinfunction "6_6") (pintype "passive"))
    )
    (net (code "73") (name "/SP_PW_A_ST") (class "Default")
      (node (ref "U1") (pin "36") (pinfunction "GPIO24_36") (pintype "bidirectional"))
    )
    (net (code "74") (name "/SP_PW_A_ST_5V") (class "Default")
      (node (ref "P3") (pin "5") (pinfunction "5_5") (pintype "passive"))
    )
    (net (code "75") (name "/STEP_X") (class "Default")
      (node (ref "U1") (pin "32") (pinfunction "GPIO21_32") (pintype "bidirectional"))
    )
    (net (code "76") (name "/STEP_X_5V") (class "Default")
      (node (ref "P5") (pin "3") (pinfunction "3_3") (pintype "passive"))
    )
    (net (code "77") (name "/STEP_Y") (class "Default")
      (node (ref "U1") (pin "34") (pinfunction "GPIO22_34") (pintype "bidirectional"))
    )
    (net (code "78") (name "/STEP_Y_5V") (class "Default")
      (node (ref "P5") (pin "4") (pinfunction "4_4") (pintype "passive"))
    )
    (net (code "79") (name "/STEP_Z") (class "Default")
      (node (ref "U1") (pin "35") (pinfunction "GPIO23_35") (pintype "bidirectional"))
    )
    (net (code "80") (name "/STEP_Z_5V") (class "Default")
      (node (ref "P5") (pin "5") (pinfunction "5_5") (pintype "passive"))
    )
    (net (code "81") (name "/STP_EN_XYZAB") (class "Default")
      (node (ref "U1") (pin "14") (pinfunction "GPIO11_14") (pintype "bidirectional"))
    )
    (net (code "82") (name "/STP_EN_XYZAB_5V") (class "Default")
      (node (ref "P3") (pin "1") (pinfunction "1_1") (pintype "passive"))
    )
    (net (code "83") (name "/TXD_EXT") (class "Default")
      (node (ref "U1") (pin "15") (pinfunction "GPIO12_15") (pintype "input"))
    )
    (net (code "85") (name "/TX_5V0") (class "Default")
      (node (ref "P5") (pin "1") (pinfunction "1_1") (pintype "passive"))
    )
    (net (code "86") (name "/USBC_CC1") (class "Default")
      (node (ref "J1") (pin "A5") (pinfunction "CC1_A5") (pintype "bidirectional"))
      (node (ref "R32") (pin "1") (pinfunction "1_1") (pintype "passive"))
    )
    (net (code "87") (name "/USBC_CC2") (class "Default")
      (node (ref "J1") (pin "B5") (pinfunction "CC2_B5") (pintype "bidirectional"))
      (node (ref "R31") (pin "1") (pinfunction "1_1") (pintype "passive"))
    )
    (net (code "88") (name "/USB_D_N") (class "Default")
      (node (ref "J1") (pin "A7") (pinfunction "DN1_A7") (pintype "bidirectional"))
      (node (ref "J1") (pin "B7") (pinfunction "DN2_B7") (pintype "bidirectional"))
      (node (ref "R4") (pin "1") (pinfunction "1_1") (pintype "passive"))
    )
    (net (code "89") (name "/USB_D_P") (class "Default")
      (node (ref "J1") (pin "A6") (pinfunction "DP1_A6") (pintype "bidirectional"))
      (node (ref "J1") (pin "B6") (pinfunction "DP2_B6") (pintype "bidirectional"))
      (node (ref "R3") (pin "1") (pinfunction "1_1") (pintype "passive"))
    )
    (net (code "90") (name "/USB_D_R_N") (class "Default")
      (node (ref "R4") (pin "2") (pinfunction "2_2") (pintype "passive"))
      (node (ref "U1") (pin "46") (pinfunction "USB_DM_46") (pintype "input"))
    )
    (net (code "91") (name "/USB_D_R_P") (class "Default")
      (node (ref "R3") (pin "2") (pinfunction "2_2") (pintype "passive"))
      (node (ref "U1") (pin "47") (pinfunction "USB_DP_47") (pintype "input"))
    )
    (net (code "92") (name "/W5500_INTn") (class "Default")
      (node (ref "U1") (pin "31") (pinfunction "GPIO20_31") (pintype "bidirectional"))
    )
    (net (code "93") (name "/WHITE") (class "Default")
      (node (ref "D8") (pin "A") (pinfunction "A_A") (pintype "passive"))
    )
    (net (code "94") (name "/X_LIM") (class "Default")
      (node (ref "U1") (pin "11") (pinfunction "GPIO8_11") (pintype "input"))
    )
    (net (code "95") (name "/X_LIM_5V") (class "Default")
      (node (ref "P3") (pin "2") (pinfunction "2_2") (pintype "passive"))
      (node (ref "R70") (pin "1") (pinfunction "1_1") (pintype "passive"))
    )
    (net (code "96") (name "/Y_LIM") (class "Default")
      (node (ref "U1") (pin "12") (pinfunction "GPIO9_12") (pintype "input"))
    )
    (net (code "97") (name "/Y_LIM_5V") (class "Default")
      (node (ref "P3") (pin "3") (pinfunction "3_3") (pintype "passive"))
      (node (ref "R13") (pin "1") (pinfunction "1_1") (pintype "passive"))
    )
    (net (code "98") (name "/Z_LIM") (class "Default")
      (node (ref "U1") (pin "41") (pinfunction "G29/A3_41") (pintype "bidirectional"))
    )
    (net (code "99") (name "/Z_LIM_5V") (class "Default")
      (node (ref "P3") (pin "4") (pinfunction "4_4") (pintype "passive"))
      (node (ref "R74") (pin "1") (pinfunction "1_1") (pintype "passive"))
    )
    (net (code "100") (name "GND") (class "Default")
      (node (ref "C1") (pin "1") (pinfunction "1_1") (pintype "passive"))
      (node (ref "C10") (pin "1") (pinfunction "1_1") (pintype "passive"))
      (node (ref "C11") (pin "1") (pinfunction "1_1") (pintype "passive"))
      (node (ref "C12") (pin "1") (pinfunction "1_1") (pintype "passive"))
      (node (ref "C13") (pin "1") (pinfunction "1_1") (pintype "passive"))
      (node (ref "C14") (pin "1") (pinfunction "1_1") (pintype "passive"))
      (node (ref "C15") (pin "1") (pinfunction "1_1") (pintype "passive"))
      (node (ref "C17") (pin "1") (pinfunction "1_1") (pintype "passive"))
      (node (ref "C18") (pin "1") (pinfunction "1_1") (pintype "passive"))
      (node (ref "C19") (pin "1") (pinfunction "1_1") (pintype "passive"))
      (node (ref "C2") (pin "1") (pinfunction "1_1") (pintype "passive"))
      (node (ref "C20") (pin "1") (pinfunction "1_1") (pintype "passive"))
      (node (ref "C21") (pin "1") (pinfunction "1_1") (pintype "passive"))
      (node (ref "C23") (pin "1") (pinfunction "1_1") (pintype "passive"))
      (node (ref "C24") (pin "1") (pinfunction "1_1") (pintype "passive"))
      (node (ref "C25") (pin "1") (pinfunction "1_1") (pintype "passive"))
      (node (ref "C26") (pin "1") (pinfunction "1_1") (pintype "passive"))
      (node (ref "C29") (pin "1") (pinfunction "1_1") (pintype "passive"))
      (node (ref "C30") (pin "1") (pinfunction "1_1") (pintype "passive"))
      (node (ref "C5") (pin "2") (pinfunction "2_2") (pintype "passive"))
      (node (ref "C50") (pin "1") (pinfunction "1_1") (pintype "passive"))
      (node (ref "C51") (pin "1") (pinfunction "1_1") (pintype "passive"))
      (node (ref "C53") (pin "1") (pinfunction "1_1") (pintype "passive"))
      (node (ref "C6") (pin "2") (pinfunction "2_2") (pintype "passive"))
      (node (ref "C7") (pin "1") (pinfunction "1_1") (pintype "passive"))
      (node (ref "C8") (pin "1") (pinfunction "1_1") (pintype "passive"))
      (node (ref "C9") (pin "1") (pinfunction "1_1") (pintype "passive"))
      (node (ref "D10") (pin "K") (pinfunction "K_K") (pintype "passive"))
      (node (ref "D13") (pin "1") (pinfunction "A_1") (pintype "passive"))
      (node (ref "D3") (pin "1") (pinfunction "A_1") (pintype "passive"))
      (node (ref "D4") (pin "1") (pinfunction "A_1") (pintype "passive"))
      (node (ref "D9") (pin "1") (pinfunction "A_1") (pintype "passive"))
      (node (ref "J1") (pin "A1B12") (pinfunction "GND_A1B12") (pintype "power_in"))
      (node (ref "J1") (pin "B1A12") (pinfunction "GND_B1A12") (pintype "power_in"))
      (node (ref "J1") (pin "S1") (pinfunction "SHIELD_S1") (pintype "passive"))
      (node (ref "J1") (pin "S2") (pinfunction "SHIELD_S2") (pintype "passive"))
      (node (ref "J1") (pin "S3") (pinfunction "SHIELD_S3") (pintype "passive"))
      (node (ref "J1") (pin "S4") (pinfunction "SHIELD_S4") (pintype "passive"))
      (node (ref "J2") (pin "2") (pinfunction "2_2") (pintype "passive"))
      (node (ref "J3") (pin "2") (pinfunction "2_2") (pintype "passive"))
      (node (ref "L1") (pin "4") (pinfunction "GND_4") (pintype "passive"))
      (node (ref "P3") (pin "7") (pinfunction "7_7") (pintype "passive"))
      (node (ref "P4") (pin "6") (pinfunction "6_6") (pintype "passive"))
      (node (ref "P4") (pin "7") (pinfunction "7_7") (pintype "passive"))
      (node (ref "P8") (pin "4") (pinfunction "4_4") (pintype "passive"))
      (node (ref "P9") (pin "1") (pinfunction "1_1") (pintype "passive"))
      (node (ref "R31") (pin "2") (pinfunction "2_2") (pintype "passive"))
      (node (ref "R32") (pin "2") (pinfunction "2_2") (pintype "passive"))
      (node (ref "R33") (pin "2") (pinfunction "2_2") (pintype "passive"))
      (node (ref "R34") (pin "2") (pinfunction "2_2") (pintype "passive"))
      (node (ref "R35") (pin "2") (pinfunction "2_2") (pintype "passive"))
      (node (ref "R36") (pin "2") (pinfunction "2_2") (pintype "passive"))
      (node (ref "SW1") (pin "1") (pinfunction "1_1") (pintype "passive"))
      (node (ref "SW1") (pin "3") (pinfunction "3_3") (pintype "passive"))
      (node (ref "SW1") (pin "MP1") (pinfunction "MP1_MP1") (pintype "passive"))
      (node (ref "SW1") (pin "MP2") (pinfunction "MP2_MP2") (pintype "passive"))
      (node (ref "SW2") (pin "1") (pinfunction "1_1") (pintype "passive"))
      (node (ref "SW2") (pin "3") (pinfunction "3_3") (pintype "passive"))
      (node (ref "SW2") (pin "MP1") (pinfunction "MP1_MP1") (pintype "passive"))
      (node (ref "SW2") (pin "MP2") (pinfunction "MP2_MP2") (pintype "passive"))
      (node (ref "U1") (pin "19") (pinfunction "TESTEN_19") (pintype "input"))
      (node (ref "U1") (pin "57") (pinfunction "PAD_GND_57") (pintype "input"))
      (node (ref "VR2") (pin "1") (pinfunction "GND_1") (pintype "passive"))
      (node (ref "Y1") (pin "2") (pinfunction "GND_1_2") (pintype "passive"))
      (node (ref "Y1") (pin "4") (pinfunction "GND_2_4") (pintype "passive"))
    )
    (net (code "101") (name "INPUT_VCC") (class "Default")
      (node (ref "FUSE1") (pin "1") (pinfunction "1_1") (pintype "passive"))
      (node (ref "J2") (pin "1") (pinfunction "1_1") (pintype "passive"))
      (node (ref "P4") (pin "8") (pinfunction "8_8") (pintype "passive"))
      (node (ref "P9") (pin "3") (pinfunction "3_3") (pintype "passive"))
    )
    (net (code "102") (name "MOD_GND") (class "Default")
      (node (ref "P10") (pin "3") (pinfunction "3_3") (pintype "passive"))
      (node (ref "P2") (pin "3") (pinfunction "3_3") (pintype "passive"))
    )
    (net (code "103") (name "Net-(D5-PadK)") (class "Default")
      (node (ref "D5") (pin "K") (pinfunction "K_K") (pintype "passive"))
      (node (ref "R33") (pin "1") (pinfunction "1_1") (pintype "passive"))
    )
    (net (code "104") (name "Net-(D6-PadK)") (class "Default")
      (node (ref "D6") (pin "K") (pinfunction "K_K") (pintype "passive"))
      (node (ref "R34") (pin "1") (pinfunction "1_1") (pintype "passive"))
    )
    (net (code "105") (name "Net-(D7-PadK)") (class "Default")
      (node (ref "D7") (pin "K") (pinfunction "K_K") (pintype "passive"))
      (node (ref "R35") (pin "1") (pinfunction "1_1") (pintype "passive"))
    )
    (net (code "106") (name "Net-(D8-PadK)") (class "Default")
      (node (ref "D8") (pin "K") (pinfunction "K_K") (pintype "passive"))
      (node (ref "R36") (pin "1") (pinfunction "1_1") (pintype "passive"))
    )
    (net (code "107") (name "Net-(D10-PadA)") (class "Default")
      (node (ref "D10") (pin "A") (pinfunction "A_A") (pintype "passive"))
      (node (ref "R10") (pin "1") (pinfunction "1_1") (pintype "passive"))
    )
    (net (code "108") (name "Net-(R2-Pad1)") (class "Default")
      (node (ref "R2") (pin "1") (pinfunction "1_1") (pintype "passive"))
      (node (ref "SW2") (pin "2") (pinfunction "2_2") (pintype "passive"))
    )
    (net (code "109") (name "Net-(Y1-CRYSTAL_2)") (class "Default")
      (node (ref "C6") (pin "1") (pinfunction "1_1") (pintype "passive"))
      (node (ref "R5") (pin "1") (pinfunction "1_1") (pintype "passive"))
      (node (ref "Y1") (pin "3") (pinfunction "CRYSTAL_2_3") (pintype "passive"))
    )
    (net (code "110") (name "Relay_VCC") (class "Default")
      (node (ref "D13") (pin "2") (pinfunction "K_2") (pintype "passive"))
      (node (ref "FUSE1") (pin "2") (pinfunction "2_2") (pintype "passive"))
      (node (ref "P1") (pin "1") (pinfunction "1_1") (pintype "passive"))
    )
    (net (code "111") (name "VREG_1V1") (class "Default")
      (node (ref "C7") (pin "2") (pinfunction "2_2") (pintype "passive"))
      (node (ref "C8") (pin "2") (pinfunction "2_2") (pintype "passive"))
      (node (ref "C9") (pin "2") (pinfunction "2_2") (pintype "passive"))
      (node (ref "U1") (pin "23") (pinfunction "DVDD_23") (pintype "input"))
      (node (ref "U1") (pin "45") (pinfunction "VREG_VOUT_45") (pintype "input"))
      (node (ref "U1") (pin "50") (pinfunction "DVDD_50") (pintype "input"))
    )
    (net (code "112") (name "unconnected-(J1-SBU1-PadA8)") (class "Default")
      (node (ref "J1") (pin "A8") (pinfunction "SBU1_A8") (pintype "bidirectional"))
    )
    (net (code "113") (name "unconnected-(J1-SBU2-PadB8)") (class "Default")
      (node (ref "J1") (pin "B8") (pinfunction "SBU2_B8") (pintype "bidirectional"))
    )
    (net (code "114") (name "unconnected-(P4-Pad1)") (class "Default")
      (node (ref "P4") (pin "1") (pinfunction "1_1") (pintype "passive"))
    )
    (net (code "115") (name "unconnected-(P4-Pad3)") (class "Default")
      (node (ref "P4") (pin "3") (pinfunction "3_3") (pintype "passive"))
    )
  )
)
